# SATELLITE_02.net
KiCad netlist of a schematic drawn in EAGLE
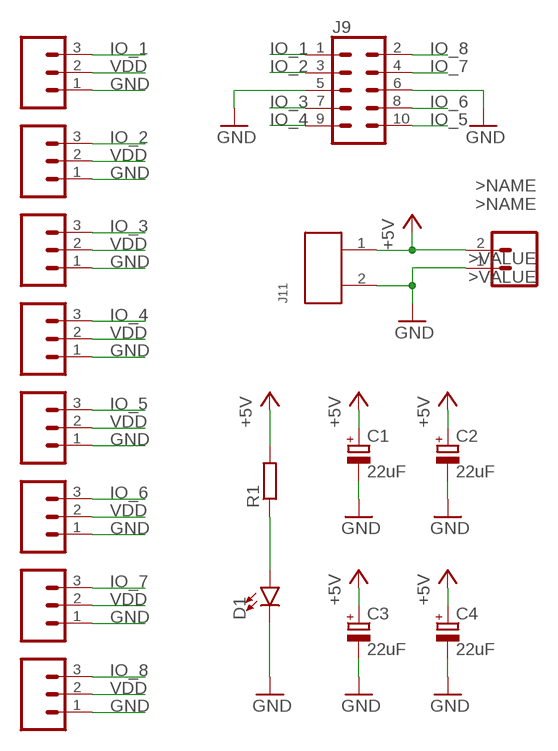
[diagram p0: schematic, sheet 1]

(export (version "E")
  (design (tool "Eeschema 10.0.6"))
  (components
    (comp (ref "C1")
      (value "22uF")
      (footprint "eagle-import:E2-5")
      (libsource (lib "eagle-import") (part "CPOL-EUE2-5"))
    )
    (comp (ref "C2")
      (value "22uF")
      (footprint "eagle-import:E2-5")
      (libsource (lib "eagle-import") (part "CPOL-EUE2-5"))
    )
    (comp (ref "C3")
      (value "22uF")
      (footprint "eagle-import:E2-5")
      (libsource (lib "eagle-import") (part "CPOL-EUE2-5"))
    )
    (comp (ref "C4")
      (value "22uF")
      (footprint "eagle-import:E2-5")
      (libsource (lib "eagle-import") (part "CPOL-EUE2-5"))
    )
    (comp (ref "D1")
      (value "LED3MM")
      (footprint "eagle-import:LED_3MM")
      (libsource (lib "eagle-import") (part "LED3MM"))
    )
    (comp (ref "J1")
      (value "CONN_03")
      (footprint "eagle-import:1X03")
      (libsource (lib "eagle-import") (part "CONN_03"))
    )
    (comp (ref "J2")
      (value "CONN_03")
      (footprint "eagle-import:1X03")
      (libsource (lib "eagle-import") (part "CONN_03"))
    )
    (comp (ref "J3")
      (value "CONN_03")
      (footprint "eagle-import:1X03")
      (libsource (lib "eagle-import") (part "CONN_03"))
    )
    (comp (ref "J4")
      (value "CONN_03")
      (footprint "eagle-import:1X03")
      (libsource (lib "eagle-import") (part "CONN_03"))
    )
    (comp (ref "J5")
      (value "CONN_03")
      (footprint "eagle-import:1X03")
      (libsource (lib "eagle-import") (part "CONN_03"))
    )
    (comp (ref "J6")
      (value "CONN_03")
      (footprint "eagle-import:1X03")
      (libsource (lib "eagle-import") (part "CONN_03"))
    )
    (comp (ref "J7")
      (value "CONN_03")
      (footprint "eagle-import:1X03")
      (libsource (lib "eagle-import") (part "CONN_03"))
    )
    (comp (ref "J8")
      (value "CONN_03")
      (footprint "eagle-import:1X03")
      (libsource (lib "eagle-import") (part "CONN_03"))
    )
    (comp (ref "J9")
      (value "CONN_05X2SHD")
      (footprint "eagle-import:2X5-SHROUDED")
      (libsource (lib "eagle-import") (part "CONN_05X2SHD"))
    )
    (comp (ref "J10")
      (value "CONN_02POLAR")
      (footprint "eagle-import:MOLEX-1X2")
      (libsource (lib "eagle-import") (part "CONN_02POLAR"))
    )
    (comp (ref "J11")
      (value "645002114822")
      (footprint "eagle-import:645002114822")
      (libsource (lib "eagle-import") (part "645002114822"))
    )
    (comp (ref "R1")
      (value "R-EU_0204/7")
      (footprint "eagle-import:0204_7")
      (libsource (lib "eagle-import") (part "R-EU_0204/7"))
    )
  )
  (nets
    (net (code "1") (name "+5V") (class "Default")
      (node (ref "C1") (pin "+") (pinfunction "+_+") (pintype "passive"))
      (node (ref "C2") (pin "+") (pinfunction "+_+") (pintype "passive"))
      (node (ref "C3") (pin "+") (pinfunction "+_+") (pintype "passive"))
      (node (ref "C4") (pin "+") (pinfunction "+_+") (pintype "passive"))
      (node (ref "J1") (pin "2") (pinfunction "2_2") (pintype "passive"))
      (node (ref "J10") (pin "2") (pinfunction "2_2") (pintype "passive"))
      (node (ref "J11") (pin "1") (pinfunction "1_1") (pintype "passive"))
      (node (ref "J2") (pin "2") (pinfunction "2_2") (pintype "passive"))
      (node (ref "J3") (pin "2") (pinfunction "2_2") (pintype "passive"))
      (node (ref "J4") (pin "2") (pinfunction "2_2") (pintype "passive"))
      (node (ref "J5") (pin "2") (pinfunction "2_2") (pintype "passive"))
      (node (ref "J6") (pin "2") (pinfunction "2_2") (pintype "passive"))
      (node (ref "J7") (pin "2") (pinfunction "2_2") (pintype "passive"))
      (node (ref "J8") (pin "2") (pinfunction "2_2") (pintype "passive"))
      (node (ref "R1") (pin "2") (pinfunction "2_2") (pintype "passive"))
    )
    (net (code "2") (name "/IO_1") (class "Default")
      (node (ref "J7") (pin "3") (pinfunction "3_3") (pintype "passive"))
      (node (ref "J9") (pin "1") (pinfunction "1_1") (pintype "passive"))
    )
    (net (code "3") (name "/IO_2") (class "Default")
      (node (ref "J8") (pin "3") (pinfunction "3_3") (pintype "passive"))
      (node (ref "J9") (pin "3") (pinfunction "3_3") (pintype "passive"))
    )
    (net (code "4") (name "/IO_3") (class "Default")
      (node (ref "J1") (pin "3") (pinfunction "3_3") (pintype "passive"))
      (node (ref "J9") (pin "7") (pinfunction "7_7") (pintype "passive"))
    )
    (net (code "5") (name "/IO_4") (class "Default")
      (node (ref "J2") (pin "3") (pinfunction "3_3") (pintype "passive"))
      (node (ref "J9") (pin "9") (pinfunction "9_9") (pintype "passive"))
    )
    (net (code "6") (name "/IO_5") (class "Default")
      (node (ref "J3") (pin "3") (pinfunction "3_3") (pintype "passive"))
      (node (ref "J9") (pin "10") (pinfunction "10_10") (pintype "passive"))
    )
    (net (code "7") (name "/IO_6") (class "Default")
      (node (ref "J4") (pin "3") (pinfunction "3_3") (pintype "passive"))
      (node (ref "J9") (pin "8") (pinfunction "8_8") (pintype "passive"))
    )
    (net (code "8") (name "/IO_7") (class "Default")
      (node (ref "J5") (pin "3") (pinfunction "3_3") (pintype "passive"))
      (node (ref "J9") (pin "4") (pinfunction "4_4") (pintype "passive"))
    )
    (net (code "9") (name "/IO_8") (class "Default")
      (node (ref "J6") (pin "3") (pinfunction "3_3") (pintype "passive"))
      (node (ref "J9") (pin "2") (pinfunction "2_2") (pintype "passive"))
    )
    (net (code "10") (name "GND") (class "Default")
      (node (ref "C1") (pin "-") (pinfunction "-_-") (pintype "passive"))
      (node (ref "C2") (pin "-") (pinfunction "-_-") (pintype "passive"))
      (node (ref "C3") (pin "-") (pinfunction "-_-") (pintype "passive"))
      (node (ref "C4") (pin "-") (pinfunction "-_-") (pintype "passive"))
      (node (ref "D1") (pin "K") (pinfunction "C_K") (pintype "passive"))
      (node (ref "J1") (pin "1") (pinfunction "1_1") (pintype "passive"))
      (node (ref "J10") (pin "1") (pinfunction "1_1") (pintype "passive"))
      (node (ref "J11") (pin "2") (pinfunction "2_2") (pintype "passive"))
      (node (ref "J2") (pin "1") (pinfunction "1_1") (pintype "passive"))
      (node (ref "J3") (pin "1") (pinfunction "1_1") (pintype "passive"))
      (node (ref "J4") (pin "1") (pinfunction "1_1") (pintype "passive"))
      (node (ref "J5") (pin "1") (pinfunction "1_1") (pintype "passive"))
      (node (ref "J6") (pin "1") (pinfunction "1_1") (pintype "passive"))
      (node (ref "J7") (pin "1") (pinfunction "1_1") (pintype "passive"))
      (node (ref "J8") (pin "1") (pinfunction "1_1") (pintype "passive"))
      (node (ref "J9") (pin "5") (pinfunction "5_5") (pintype "passive"))
      (node (ref "J9") (pin "6") (pinfunction "6_6") (pintype "passive"))
    )
    (net (code "11") (name "Net-(D1-PadA)") (class "Default")
      (node (ref "D1") (pin "A") (pinfunction "A_A") (pintype "passive"))
      (node (ref "R1") (pin "1") (pinfunction "1_1") (pintype "passive"))
    )
  )
)
